# SOT-23-8-Adapter.net
KiCad netlist of a schematic drawn in EAGLE
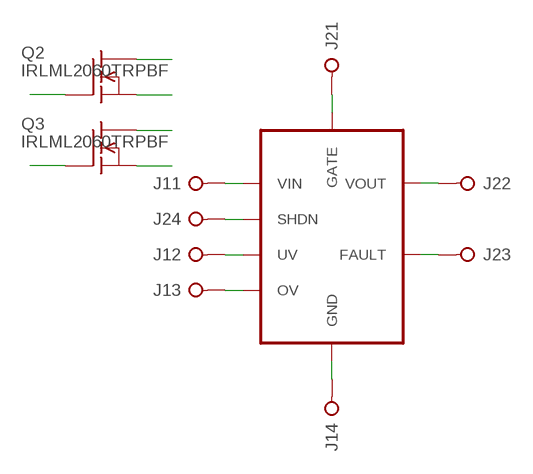
[diagram p0: schematic, sheet 1]

(export (version "E")
  (design (tool "Eeschema 10.0.6"))
  (components
    (comp (ref "J1")
      (value "PINHD-1X4")
      (footprint "eagle-import:1X04")
      (libsource (lib "eagle-import") (part "PINHD-1X4"))
    )
    (comp (ref "J2")
      (value "PINHD-1X4")
      (footprint "eagle-import:1X04")
      (libsource (lib "eagle-import") (part "PINHD-1X4"))
    )
    (comp (ref "Q1")
      (value "LTC4365")
      (footprint "eagle-import:SOT-23-8")
      (libsource (lib "eagle-import") (part "LTC4365"))
    )
    (comp (ref "Q2")
      (value "IRLML2060TRPBF")
      (footprint "eagle-import:SOT-23-3")
      (libsource (lib "eagle-import") (part "IRLML2060TRPBF"))
    )
    (comp (ref "Q3")
      (value "IRLML2060TRPBF")
      (footprint "eagle-import:SOT-23-3")
      (libsource (lib "eagle-import") (part "IRLML2060TRPBF"))
    )
  )
  (nets
    (net (code "1") (name "/1-1") (class "Default")
      (node (ref "J1") (pin "1") (pinfunction "KL_1") (pintype "passive"))
      (node (ref "Q1") (pin "1") (pinfunction "VIN_1") (pintype "power_in"))
      (node (ref "Q2") (pin "2") (pinfunction "SRC_2") (pintype "passive"))
    )
    (net (code "2") (name "/1-2") (class "Default")
      (node (ref "J1") (pin "2") (pinfunction "KL_2") (pintype "passive"))
      (node (ref "Q1") (pin "2") (pinfunction "UV_2") (pintype "input"))
      (node (ref "Q2") (pin "1") (pinfunction "GATE_1") (pintype "passive"))
    )
    (net (code "3") (name "/1-3") (class "Default")
      (node (ref "J1") (pin "3") (pinfunction "KL_3") (pintype "passive"))
      (node (ref "Q1") (pin "3") (pinfunction "OV_3") (pintype "input"))
      (node (ref "Q3") (pin "2") (pinfunction "SRC_2") (pintype "passive"))
    )
    (net (code "4") (name "/1-4") (class "Default")
      (node (ref "J1") (pin "4") (pinfunction "KL_4") (pintype "passive"))
      (node (ref "Q1") (pin "4") (pinfunction "GND_4") (pintype "passive"))
      (node (ref "Q3") (pin "1") (pinfunction "GATE_1") (pintype "passive"))
    )
    (net (code "5") (name "/2-1") (class "Default")
      (node (ref "J2") (pin "1") (pinfunction "KL_1") (pintype "passive"))
      (node (ref "Q1") (pin "8") (pinfunction "GATE_8") (pintype "output"))
      (node (ref "Q2") (pin "3") (pinfunction "DRN_3") (pintype "passive"))
    )
    (net (code "6") (name "/2-4") (class "Default")
      (node (ref "J2") (pin "4") (pinfunction "KL_4") (pintype "passive"))
      (node (ref "Q1") (pin "5") (pinfunction "SHDN_5") (pintype "input"))
      (node (ref "Q3") (pin "3") (pinfunction "DRN_3") (pintype "passive"))
    )
    (net (code "7") (name "Net-(J2B-KL)") (class "Default")
      (node (ref "J2") (pin "2") (pinfunction "KL_2") (pintype "passive"))
      (node (ref "Q1") (pin "7") (pinfunction "VOUT_7") (pintype "input"))
    )
    (net (code "8") (name "Net-(J2C-KL)") (class "Default")
      (node (ref "J2") (pin "3") (pinfunction "KL_3") (pintype "passive"))
      (node (ref "Q1") (pin "6") (pinfunction "FAULT_6") (pintype "output"))
    )
  )
)
